# EpyxFastLoad.net
KiCad netlist of a schematic drawn in EAGLE
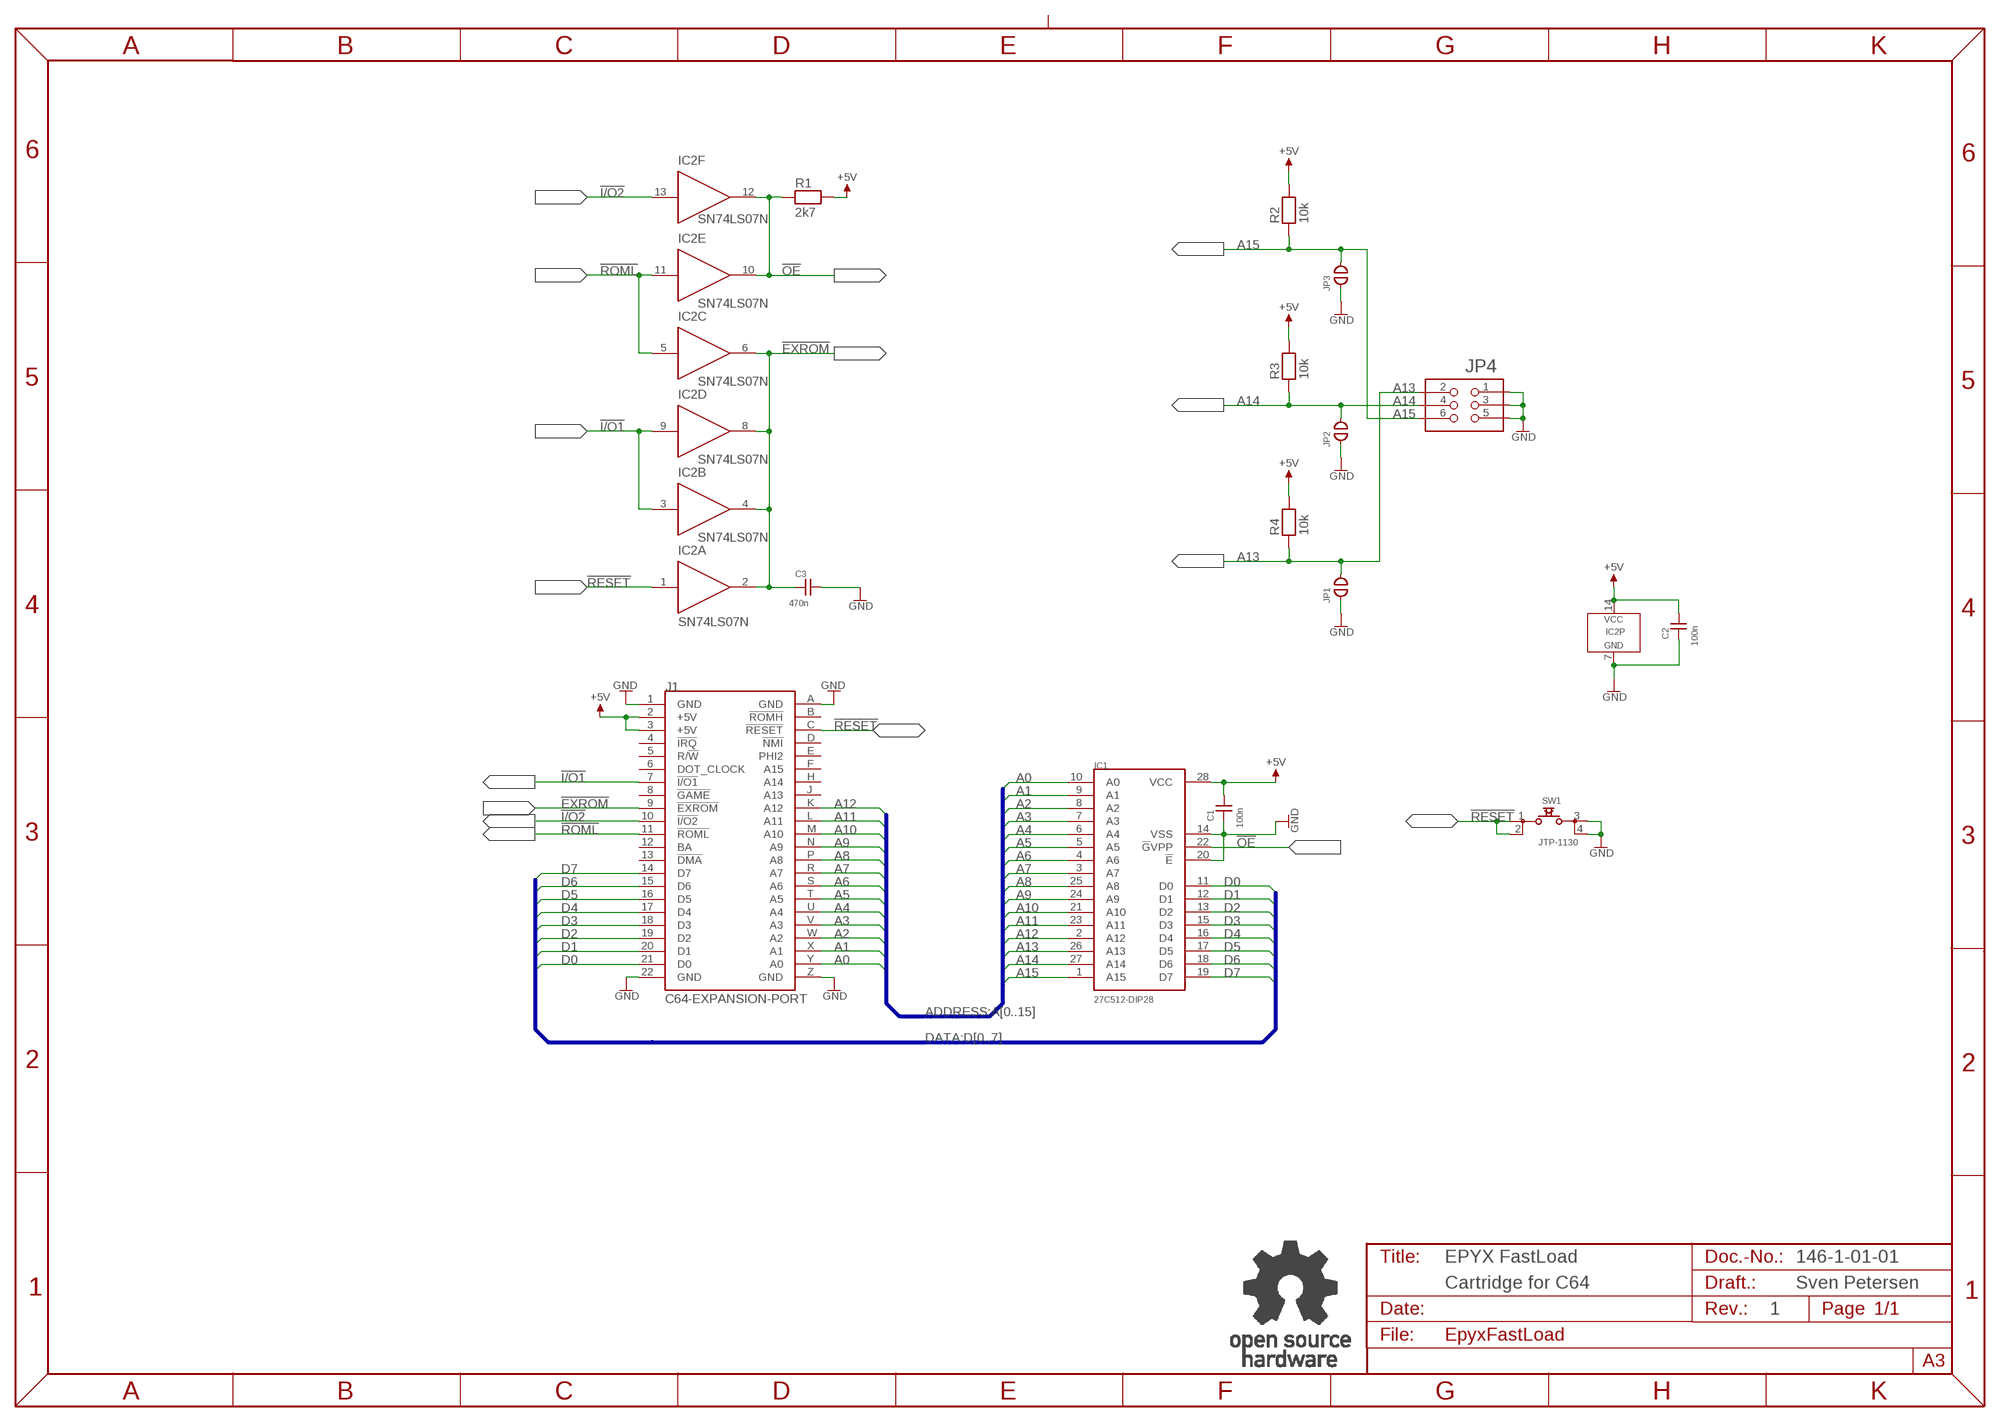
[diagram p0: schematic, sheet 1]

(export (version "E")
  (design (tool "Eeschema 10.0.6"))
  (components
    (comp (ref "C1")
      (value "100n")
      (footprint "eagle-import:C-2,5")
      (libsource (lib "eagle-import") (part "CAP01"))
    )
    (comp (ref "C2")
      (value "100n")
      (footprint "eagle-import:C-2,5")
      (libsource (lib "eagle-import") (part "CAP01"))
    )
    (comp (ref "C3")
      (value "470n")
      (footprint "eagle-import:C-5")
      (libsource (lib "eagle-import") (part "CAP02"))
    )
    (comp (ref "IC1")
      (value "27C512-DIP28")
      (footprint "eagle-import:DIL28-6")
      (libsource (lib "eagle-import") (part "M27C512-DIP28"))
    )
    (comp (ref "IC2")
      (value "SN74LS07N")
      (footprint "eagle-import:DIL-14")
      (libsource (lib "eagle-import") (part "7407N"))
    )
    (comp (ref "J1")
      (value "C64-EXPANSION-PORT")
      (footprint "eagle-import:EXPANSIO_SQ")
      (libsource (lib "eagle-import") (part "C64-EXPANSIONPNARROW"))
    )
    (comp (ref "JP1")
      (value "OPEN")
      (footprint "eagle-import:CP_OP")
      (libsource (lib "eagle-import") (part "OPEN"))
    )
    (comp (ref "JP2")
      (value "OPEN")
      (footprint "eagle-import:CP_OP")
      (libsource (lib "eagle-import") (part "OPEN"))
    )
    (comp (ref "JP3")
      (value "OPEN")
      (footprint "eagle-import:CP_OP")
      (libsource (lib "eagle-import") (part "OPEN"))
    )
    (comp (ref "JP4")
      (value "PINHD-2X390°")
      (footprint "eagle-import:2X03_90_SERIES_088")
      (libsource (lib "eagle-import") (part "PINHD-2X390°"))
    )
    (comp (ref "R1")
      (value "2k7")
      (footprint "eagle-import:R-10")
      (libsource (lib "eagle-import") (part "RES04"))
    )
    (comp (ref "R2")
      (value "10k")
      (footprint "eagle-import:R-10")
      (libsource (lib "eagle-import") (part "RES04"))
    )
    (comp (ref "R3")
      (value "10k")
      (footprint "eagle-import:R-10")
      (libsource (lib "eagle-import") (part "RES04"))
    )
    (comp (ref "R4")
      (value "10k")
      (footprint "eagle-import:R-10")
      (libsource (lib "eagle-import") (part "RES04"))
    )
    (comp (ref "SW1")
      (value "JTP-1130")
      (footprint "eagle-import:JTP-1130")
      (libsource (lib "eagle-import") (part "JTP-1130"))
    )
    (comp (ref "U$39")
      (value "OPEN_SOURCE_HW")
      (footprint "eagle-import:OPENHW")
      (libsource (lib "eagle-import") (part "OPEN_SOURCE_HW"))
    )
  )
  (nets
    (net (code "25") (name "+5V") (class "Default")
      (node (ref "C1") (pin "2") (pinfunction "2_2") (pintype "passive"))
      (node (ref "C2") (pin "2") (pinfunction "2_2") (pintype "passive"))
      (node (ref "IC1") (pin "28") (pinfunction "VCC_28") (pintype "power_in"))
      (node (ref "IC2") (pin "14") (pinfunction "VCC_14") (pintype "bidirectional"))
      (node (ref "J1") (pin "2") (pinfunction "+5V_2") (pintype "power_in"))
      (node (ref "J1") (pin "3") (pinfunction "+5V_3") (pintype "power_in"))
      (node (ref "R1") (pin "2") (pinfunction "2_2") (pintype "passive"))
      (node (ref "R2") (pin "2") (pinfunction "2_2") (pintype "passive"))
      (node (ref "R3") (pin "2") (pinfunction "2_2") (pintype "passive"))
      (node (ref "R4") (pin "2") (pinfunction "2_2") (pintype "passive"))
    )
    (net (code "26") (name "/A0") (class "Default")
      (node (ref "IC1") (pin "10") (pinfunction "A0_10") (pintype "input"))
      (node (ref "J1") (pin "Y") (pinfunction "A0_Y") (pintype "bidirectional"))
    )
    (net (code "27") (name "/A1") (class "Default")
      (node (ref "IC1") (pin "9") (pinfunction "A1_9") (pintype "input"))
      (node (ref "J1") (pin "X") (pinfunction "A1_X") (pintype "bidirectional"))
    )
    (net (code "28") (name "/A2") (class "Default")
      (node (ref "IC1") (pin "8") (pinfunction "A2_8") (pintype "input"))
      (node (ref "J1") (pin "W") (pinfunction "A2_W") (pintype "bidirectional"))
    )
    (net (code "29") (name "/A3") (class "Default")
      (node (ref "IC1") (pin "7") (pinfunction "A3_7") (pintype "input"))
      (node (ref "J1") (pin "V") (pinfunction "A3_V") (pintype "bidirectional"))
    )
    (net (code "30") (name "/A4") (class "Default")
      (node (ref "IC1") (pin "6") (pinfunction "A4_6") (pintype "input"))
      (node (ref "J1") (pin "U") (pinfunction "A4_U") (pintype "bidirectional"))
    )
    (net (code "31") (name "/A5") (class "Default")
      (node (ref "IC1") (pin "5") (pinfunction "A5_5") (pintype "input"))
      (node (ref "J1") (pin "T") (pinfunction "A5_T") (pintype "bidirectional"))
    )
    (net (code "32") (name "/A6") (class "Default")
      (node (ref "IC1") (pin "4") (pinfunction "A6_4") (pintype "input"))
      (node (ref "J1") (pin "S") (pinfunction "A6_S") (pintype "bidirectional"))
    )
    (net (code "33") (name "/A7") (class "Default")
      (node (ref "IC1") (pin "3") (pinfunction "A7_3") (pintype "input"))
      (node (ref "J1") (pin "R") (pinfunction "A7_R") (pintype "bidirectional"))
    )
    (net (code "34") (name "/A8") (class "Default")
      (node (ref "IC1") (pin "25") (pinfunction "A8_25") (pintype "input"))
      (node (ref "J1") (pin "P") (pinfunction "A8_P") (pintype "bidirectional"))
    )
    (net (code "35") (name "/A9") (class "Default")
      (node (ref "IC1") (pin "24") (pinfunction "A9_24") (pintype "input"))
      (node (ref "J1") (pin "N") (pinfunction "A9_N") (pintype "bidirectional"))
    )
    (net (code "36") (name "/A10") (class "Default")
      (node (ref "IC1") (pin "21") (pinfunction "A10_21") (pintype "input"))
      (node (ref "J1") (pin "M") (pinfunction "A10_M") (pintype "bidirectional"))
    )
    (net (code "37") (name "/A11") (class "Default")
      (node (ref "IC1") (pin "23") (pinfunction "A11_23") (pintype "input"))
      (node (ref "J1") (pin "L") (pinfunction "A11_L") (pintype "bidirectional"))
    )
    (net (code "38") (name "/A12") (class "Default")
      (node (ref "IC1") (pin "2") (pinfunction "A12_2") (pintype "input"))
      (node (ref "J1") (pin "K") (pinfunction "A12_K") (pintype "bidirectional"))
    )
    (net (code "39") (name "/A13") (class "Default")
      (node (ref "IC1") (pin "26") (pinfunction "A13_26") (pintype "input"))
      (node (ref "JP1") (pin "2") (pinfunction "2_2") (pintype "passive"))
      (node (ref "JP4") (pin "2") (pinfunction "2_2") (pintype "passive"))
      (node (ref "R4") (pin "1") (pinfunction "1_1") (pintype "passive"))
    )
    (net (code "40") (name "/A14") (class "Default")
      (node (ref "IC1") (pin "27") (pinfunction "A14_27") (pintype "input"))
      (node (ref "JP2") (pin "2") (pinfunction "2_2") (pintype "passive"))
      (node (ref "JP4") (pin "4") (pinfunction "4_4") (pintype "passive"))
      (node (ref "R3") (pin "1") (pinfunction "1_1") (pintype "passive"))
    )
    (net (code "41") (name "/A15") (class "Default")
      (node (ref "IC1") (pin "1") (pinfunction "A15_1") (pintype "input"))
      (node (ref "JP3") (pin "2") (pinfunction "2_2") (pintype "passive"))
      (node (ref "JP4") (pin "6") (pinfunction "6_6") (pintype "passive"))
      (node (ref "R2") (pin "1") (pinfunction "1_1") (pintype "passive"))
    )
    (net (code "43") (name "/D0") (class "Default")
      (node (ref "IC1") (pin "11") (pinfunction "D0_11") (pintype "bidirectional"))
      (node (ref "J1") (pin "21") (pinfunction "D0_21") (pintype "bidirectional"))
    )
    (net (code "44") (name "/D1") (class "Default")
      (node (ref "IC1") (pin "12") (pinfunction "D1_12") (pintype "bidirectional"))
      (node (ref "J1") (pin "20") (pinfunction "D1_20") (pintype "bidirectional"))
    )
    (net (code "45") (name "/D2") (class "Default")
      (node (ref "IC1") (pin "13") (pinfunction "D2_13") (pintype "bidirectional"))
      (node (ref "J1") (pin "19") (pinfunction "D2_19") (pintype "bidirectional"))
    )
    (net (code "46") (name "/D3") (class "Default")
      (node (ref "IC1") (pin "15") (pinfunction "D3_15") (pintype "bidirectional"))
      (node (ref "J1") (pin "18") (pinfunction "D3_18") (pintype "bidirectional"))
    )
    (net (code "47") (name "/D4") (class "Default")
      (node (ref "IC1") (pin "16") (pinfunction "D4_16") (pintype "bidirectional"))
      (node (ref "J1") (pin "17") (pinfunction "D4_17") (pintype "bidirectional"))
    )
    (net (code "48") (name "/D5") (class "Default")
      (node (ref "IC1") (pin "17") (pinfunction "D5_17") (pintype "bidirectional"))
      (node (ref "J1") (pin "16") (pinfunction "D5_16") (pintype "bidirectional"))
    )
    (net (code "49") (name "/D6") (class "Default")
      (node (ref "IC1") (pin "18") (pinfunction "D6_18") (pintype "bidirectional"))
      (node (ref "J1") (pin "15") (pinfunction "D6_15") (pintype "bidirectional"))
    )
    (net (code "50") (name "/D7") (class "Default")
      (node (ref "IC1") (pin "19") (pinfunction "D7_19") (pintype "bidirectional"))
      (node (ref "J1") (pin "14") (pinfunction "D7_14") (pintype "bidirectional"))
    )
    (net (code "52") (name "/~{EXROM}") (class "Default")
      (node (ref "C3") (pin "1") (pinfunction "1_1") (pintype "passive"))
      (node (ref "IC2") (pin "2") (pinfunction "O_2") (pintype "open_collector"))
      (node (ref "IC2") (pin "4") (pinfunction "O_4") (pintype "open_collector"))
      (node (ref "IC2") (pin "6") (pinfunction "O_6") (pintype "open_collector"))
      (node (ref "IC2") (pin "8") (pinfunction "O_8") (pintype "open_collector"))
      (node (ref "J1") (pin "9") (pinfunction "~{EXROM}_9") (pintype "input"))
    )
    (net (code "53") (name "/~{I{slash}O1}") (class "Default")
      (node (ref "IC2") (pin "3") (pinfunction "I_3") (pintype "input"))
      (node (ref "IC2") (pin "9") (pinfunction "I_9") (pintype "input"))
      (node (ref "J1") (pin "7") (pinfunction "~{I/O1}_7") (pintype "output"))
    )
    (net (code "54") (name "/~{I{slash}O2}") (class "Default")
      (node (ref "IC2") (pin "13") (pinfunction "I_13") (pintype "input"))
      (node (ref "J1") (pin "10") (pinfunction "~{I/O2}_10") (pintype "output"))
    )
    (net (code "55") (name "/~{OE}") (class "Default")
      (node (ref "IC1") (pin "22") (pinfunction "~{G}VPP_22") (pintype "input"))
      (node (ref "IC2") (pin "10") (pinfunction "O_10") (pintype "open_collector"))
      (node (ref "IC2") (pin "12") (pinfunction "O_12") (pintype "open_collector"))
      (node (ref "R1") (pin "1") (pinfunction "1_1") (pintype "passive"))
    )
    (net (code "56") (name "/~{RESET}") (class "Default")
      (node (ref "IC2") (pin "1") (pinfunction "I_1") (pintype "input"))
      (node (ref "J1") (pin "C") (pinfunction "~{RESET}_C") (pintype "open_collector"))
      (node (ref "SW1") (pin "1") (pinfunction "1_1") (pintype "passive"))
      (node (ref "SW1") (pin "2") (pinfunction "2_2") (pintype "passive"))
    )
    (net (code "57") (name "/~{ROML}") (class "Default")
      (node (ref "IC2") (pin "11") (pinfunction "I_11") (pintype "input"))
      (node (ref "IC2") (pin "5") (pinfunction "I_5") (pintype "input"))
      (node (ref "J1") (pin "11") (pinfunction "~{ROML}_11") (pintype "output"))
    )
    (net (code "58") (name "GND") (class "Default")
      (node (ref "C1") (pin "1") (pinfunction "1_1") (pintype "passive"))
      (node (ref "C2") (pin "1") (pinfunction "1_1") (pintype "passive"))
      (node (ref "C3") (pin "2") (pinfunction "2_2") (pintype "passive"))
      (node (ref "IC1") (pin "14") (pinfunction "VSS_14") (pintype "power_in"))
      (node (ref "IC1") (pin "20") (pinfunction "~{E}_20") (pintype "input"))
      (node (ref "IC2") (pin "7") (pinfunction "GND_7") (pintype "bidirectional"))
      (node (ref "J1") (pin "1") (pinfunction "GND_1") (pintype "power_in"))
      (node (ref "J1") (pin "22") (pinfunction "GND_22") (pintype "power_in"))
      (node (ref "J1") (pin "A") (pinfunction "GND_A") (pintype "power_in"))
      (node (ref "J1") (pin "Z") (pinfunction "GND_Z") (pintype "power_in"))
      (node (ref "JP1") (pin "1") (pinfunction "1_1") (pintype "passive"))
      (node (ref "JP2") (pin "1") (pinfunction "1_1") (pintype "passive"))
      (node (ref "JP3") (pin "1") (pinfunction "1_1") (pintype "passive"))
      (node (ref "JP4") (pin "1") (pinfunction "1_1") (pintype "passive"))
      (node (ref "JP4") (pin "3") (pinfunction "3_3") (pintype "passive"))
      (node (ref "JP4") (pin "5") (pinfunction "5_5") (pintype "passive"))
      (node (ref "SW1") (pin "3") (pinfunction "3_3") (pintype "passive"))
      (node (ref "SW1") (pin "4") (pinfunction "4_4") (pintype "passive"))
    )
    (net (code "59") (name "unconnected-(J1-A13-PadJ)") (class "Default")
      (node (ref "J1") (pin "J") (pinfunction "A13_J") (pintype "bidirectional"))
    )
    (net (code "60") (name "unconnected-(J1-A14-PadH)") (class "Default")
      (node (ref "J1") (pin "H") (pinfunction "A14_H") (pintype "bidirectional"))
    )
    (net (code "61") (name "unconnected-(J1-A15-PadF)") (class "Default")
      (node (ref "J1") (pin "F") (pinfunction "A15_F") (pintype "bidirectional"))
    )
    (net (code "62") (name "unconnected-(J1-BA-Pad12)") (class "Default")
      (node (ref "J1") (pin "12") (pinfunction "BA_12") (pintype "output"))
    )
    (net (code "63") (name "unconnected-(J1-DOT_CLOCK-Pad6)") (class "Default")
      (node (ref "J1") (pin "6") (pinfunction "DOT_CLOCK_6") (pintype "output"))
    )
    (net (code "64") (name "unconnected-(J1-PHI2-PadE)") (class "Default")
      (node (ref "J1") (pin "E") (pinfunction "PHI2_E") (pintype "output"))
    )
    (net (code "65") (name "unconnected-(J1-R{slash}~{W}-Pad5)") (class "Default")
      (node (ref "J1") (pin "5") (pinfunction "R/~{W}_5") (pintype "output"))
    )
    (net (code "66") (name "unconnected-(J1-~{DMA}-Pad13)") (class "Default")
      (node (ref "J1") (pin "13") (pinfunction "~{DMA}_13") (pintype "input"))
    )
    (net (code "67") (name "unconnected-(J1-~{GAME}-Pad8)") (class "Default")
      (node (ref "J1") (pin "8") (pinfunction "~{GAME}_8") (pintype "input"))
    )
    (net (code "68") (name "unconnected-(J1-~{IRQ}-Pad4)") (class "Default")
      (node (ref "J1") (pin "4") (pinfunction "~{IRQ}_4") (pintype "input"))
    )
    (net (code "69") (name "unconnected-(J1-~{NMI}-PadD)") (class "Default")
      (node (ref "J1") (pin "D") (pinfunction "~{NMI}_D") (pintype "input"))
    )
    (net (code "70") (name "unconnected-(J1-~{ROMH}-PadB)") (class "Default")
      (node (ref "J1") (pin "B") (pinfunction "~{ROMH}_B") (pintype "output"))
    )
  )
)
